# Power.net
KiCad netlist of a schematic drawn in Altium Designer
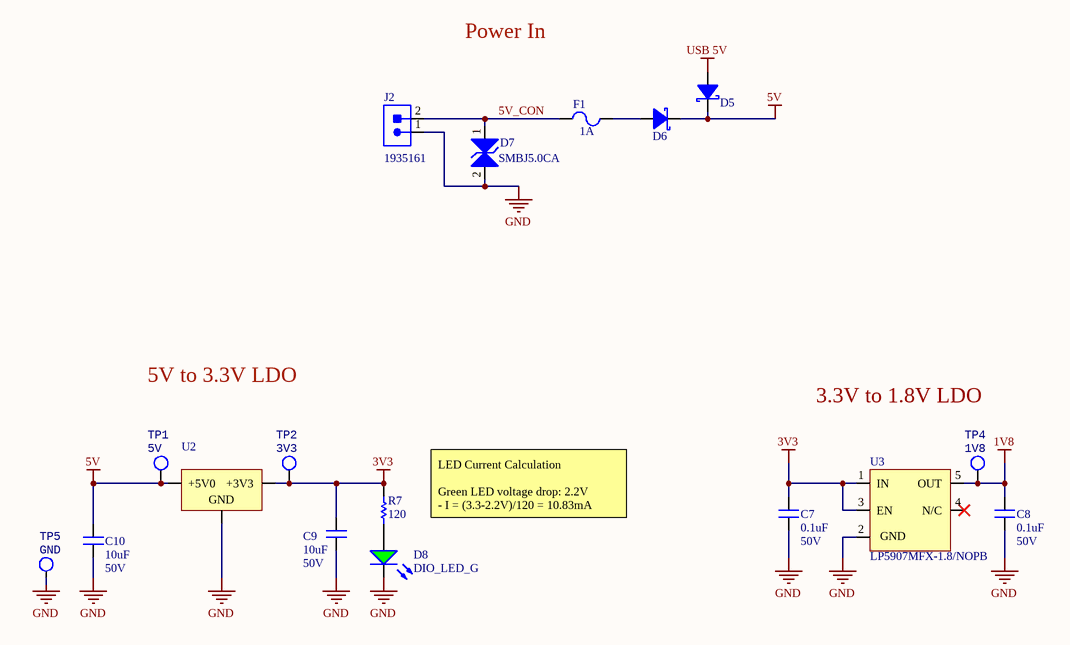
[diagram p0: Power.SchDoc]

(export (version "E")
  (design (tool "Eeschema 10.0.6"))
  (components
    (comp (ref "C7")
      (value "0.1uF")
      (footprint "CAPC2012X140N")
      (description "CAP CER 0.1UF 50V X7R 0805")
      (fields
        (field (name "TOLERANCE") "10%")
        (field (name "VOLTAGE RATING") "50V")
        (field (name "Comment") "CAP_0.1uF_50V_0805")
      )
      (libsource (lib "UWRT_Schematic_Library_2020") (part "CAP_0.1uF_50V_0805"))
    )
    (comp (ref "C8")
      (value "0.1uF")
      (footprint "CAPC2012X140N")
      (description "CAP CER 0.1UF 50V X7R 0805")
      (fields
        (field (name "TOLERANCE") "10%")
        (field (name "VOLTAGE RATING") "50V")
        (field (name "Comment") "CAP_0.1uF_50V_0805")
      )
      (libsource (lib "UWRT_Schematic_Library_2020") (part "CAP_0.1uF_50V_0805"))
    )
    (comp (ref "C9")
      (value "10uF")
      (footprint "CAPC1206(3216)")
      (description "CAP CER 10UF 50V X5R 1206")
      (fields (field (name "VOLTAGE RATING") "50V"))
      (libsource (lib "UWRT_Schematic_Library_2020") (part "CAP_10uF_50V_1206"))
    )
    (comp (ref "C10")
      (value "10uF")
      (footprint "CAPC1206(3216)")
      (description "CAP CER 10UF 50V X5R 1206")
      (fields (field (name "VOLTAGE RATING") "50V"))
      (libsource (lib "UWRT_Schematic_Library_2020") (part "CAP_10uF_50V_1206"))
    )
    (comp (ref "D5")
      (value "DIO_SCHOTTKY_30V_800mA")
      (footprint "DIO_CUS520,H3F")
      (description "DIODE SCHOTTKY 30V 800MA USC")
      (libsource (lib "UWRT_Schematic_Library_2020") (part "DIO_SCHOTTKY_30V_800mA"))
    )
    (comp (ref "D6")
      (value "DIO_SCHOTTKY_30V_800mA")
      (footprint "DIO_CUS520,H3F")
      (description "DIODE SCHOTTKY 30V 800MA USC")
      (libsource (lib "UWRT_Schematic_Library_2020") (part "DIO_SCHOTTKY_30V_800mA"))
    )
    (comp (ref "D7")
      (value "TVS_DIODE_BIDIR_5V")
      (footprint "TVS_DIODE_BIDIRECTIONAL")
      (description "TVS DIODE 5V 9.2V DO214AA")
      (fields (field (name "MANUFACTURER PART NUMBER 1") "SMBJ5.0CA"))
      (libsource (lib "UWRT_Schematic_Library_2020") (part "TVS_DIODE_BIDIR_5V"))
    )
    (comp (ref "D8")
      (value "DIO_LED_G")
      (footprint "LED_0805_LINE")
      (description "LED GREEN DIFFUSED 0805 SMD")
      (libsource (lib "UWRT_Schematic_Library_2020") (part "DIO_LED_G"))
    )
    (comp (ref "F1")
      (value "FUSE_1A_1206")
      (footprint "FUSC3215X78N")
      (description "FUSE BOARD MOUNT 1A 125VAC 63VDC")
      (fields (field (name "CURRENT RATING") "1A"))
      (libsource (lib "UWRT_Schematic_Library_2020") (part "FUSE_1A_1206"))
    )
    (comp (ref "J2")
      (value "CON_2M_TERM")
      (footprint "1935161")
      (description "TERM BLK 2POS SIDE ENTRY 5MM")
      (fields (field (name "MANUFACTURER PART NUMBER 1") "1935161") (field (name "VOLTAGE") "300V"))
      (libsource (lib "UWRT_Schematic_Library_2020") (part "CON_2M_TERM"))
    )
    (comp (ref "R7")
      (value "120")
      (footprint "RESC0603(1608)_N")
      (description "RES SMD 120 OHM 5% 1/10W 0603")
      (fields (field (name "TOLERANCE") "5%") (field (name "Comment") "RES_120R_0603"))
      (libsource (lib "UWRT_Schematic_Library_2020") (part "RES_120R_0603"))
    )
    (comp (ref "TP1")
      (value "5V")
      (footprint "TESTPOINT_LOOP")
      (description "Loop testpoint through-hole pad")
      (libsource (lib "UWRT_Schematic_Library_2020") (part "TESTPOINT_LOOP"))
    )
    (comp (ref "TP2")
      (value "3V3")
      (footprint "TESTPOINT_LOOP")
      (description "Loop testpoint through-hole pad")
      (libsource (lib "UWRT_Schematic_Library_2020") (part "TESTPOINT_LOOP"))
    )
    (comp (ref "TP4")
      (value "1V8")
      (footprint "TESTPOINT_LOOP")
      (description "Loop testpoint through-hole pad")
      (libsource (lib "UWRT_Schematic_Library_2020") (part "TESTPOINT_LOOP"))
    )
    (comp (ref "TP5")
      (value "GND")
      (footprint "TESTPOINT_LOOP")
      (description "Loop testpoint through-hole pad")
      (libsource (lib "UWRT_Schematic_Library_2020") (part "TESTPOINT_LOOP"))
    )
    (comp (ref "U2")
      (value "5V0_3V3_LDO")
      (footprint "VOLTAGE_REGULATOR")
      (description "IC REG LINEAR 3.3V 1A DPAK")
      (libsource (lib "UWRT_Schematic_Library_2020") (part "5V0_3V3_LDO"))
    )
    (comp (ref "U3")
      (value "LDO_1.8V_250mA")
      (footprint "UWRT_Footprint_Library_2020:LP5907MFX-1.8/NOPB")
      (description "IC REG LINEAR 1.8V 250MA SOT23-5")
      (fields (field (name "MANUFACTURER PART NUMBER 1") "LP5907MFX-1.8/NOPB"))
      (libsource (lib "UWRT_Schematic_Library_2020") (part "LDO_1.8V_250mA"))
    )
  )
  (nets
    (net (code "1") (name "/5V_CON") (class "Default")
      (node (ref "D7") (pin "1") (pinfunction "1_1") (pintype "passive"))
      (node (ref "F1") (pin "1") (pinfunction "1_1") (pintype "passive"))
      (node (ref "J2") (pin "2") (pinfunction "2_2") (pintype "passive"))
    )
    (net (code "2") (name "1V8") (class "Default")
      (node (ref "C8") (pin "2") (pinfunction "2_2") (pintype "passive"))
      (node (ref "TP4") (pin "1") (pintype "passive"))
      (node (ref "U3") (pin "5") (pinfunction "OUT_5") (pintype "passive"))
    )
    (net (code "3") (name "3V3") (class "Default")
      (node (ref "C7") (pin "2") (pinfunction "2_2") (pintype "passive"))
      (node (ref "C9") (pin "2") (pinfunction "2_2") (pintype "passive"))
      (node (ref "R7") (pin "2") (pinfunction "2_2") (pintype "passive"))
      (node (ref "TP2") (pin "1") (pintype "passive"))
      (node (ref "U2") (pin "2") (pinfunction "+3V3_2") (pintype "passive"))
      (node (ref "U3") (pin "1") (pinfunction "IN_1") (pintype "passive"))
      (node (ref "U3") (pin "3") (pinfunction "EN_3") (pintype "passive"))
    )
    (net (code "4") (name "5V") (class "Default")
      (node (ref "C10") (pin "2") (pinfunction "2_2") (pintype "passive"))
      (node (ref "D5") (pin "2") (pinfunction "Cathode_2") (pintype "passive"))
      (node (ref "D6") (pin "2") (pinfunction "Cathode_2") (pintype "passive"))
      (node (ref "TP1") (pin "1") (pintype "passive"))
      (node (ref "U2") (pin "3") (pinfunction "+5V0_3") (pintype "passive"))
    )
    (net (code "5") (name "GND") (class "Default")
      (node (ref "C10") (pin "1") (pinfunction "1_1") (pintype "passive"))
      (node (ref "C7") (pin "1") (pinfunction "1_1") (pintype "passive"))
      (node (ref "C8") (pin "1") (pinfunction "1_1") (pintype "passive"))
      (node (ref "C9") (pin "1") (pinfunction "1_1") (pintype "passive"))
      (node (ref "D7") (pin "2") (pinfunction "2_2") (pintype "passive"))
      (node (ref "D8") (pin "2") (pinfunction "K_2") (pintype "passive"))
      (node (ref "J2") (pin "1") (pinfunction "1_1") (pintype "passive"))
      (node (ref "TP5") (pin "1") (pintype "passive"))
      (node (ref "U2") (pin "1") (pinfunction "GND_1") (pintype "passive"))
      (node (ref "U3") (pin "2") (pinfunction "GND_2") (pintype "passive"))
    )
    (net (code "6") (name "Net-(D6-Anode)") (class "Default")
      (node (ref "D6") (pin "1") (pinfunction "Anode_1") (pintype "passive"))
      (node (ref "F1") (pin "2") (pinfunction "2_2") (pintype "passive"))
    )
    (net (code "7") (name "Net-(D8-A)") (class "Default")
      (node (ref "D8") (pin "1") (pinfunction "A_1") (pintype "passive"))
      (node (ref "R7") (pin "1") (pinfunction "1_1") (pintype "passive"))
    )
    (net (code "8") (name "USB 5V") (class "Default")
      (node (ref "D5") (pin "1") (pinfunction "Anode_1") (pintype "passive"))
    )
    (net (code "9") (name "unconnected-(U3-N{slash}C-Pad4)") (class "Default")
      (node (ref "U3") (pin "4") (pinfunction "N/C_4") (pintype "passive+no_connect"))
    )
  )
)
